# Vert_1.net
KiCad netlist of a schematic drawn in Altium Designer
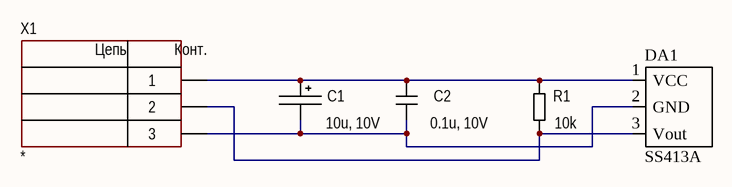
[diagram p0: Vert_1.SchDoc]

(export (version "E")
  (design (tool "Eeschema 10.0.6"))
  (components
    (comp (ref "C1")
      (value "10u, 10V")
      (footprint "TANTAL_A")
      (libsource (lib "Condensators") (part "TantalCap"))
    )
    (comp (ref "C2")
      (value "0.1u, 10V")
      (footprint "CH0603C")
      (libsource (lib "Condensators") (part "Capacitor"))
    )
    (comp (ref "DA1") (value "SS413A") (libsource (lib "BufLib") (part "SS413A")))
    (comp (ref "R1") (value "10k") (footprint "CH0603R") (libsource (lib "Resistors") (part "Resistor")))
    (comp (ref "X1")
      (value "*")
      (footprint "CON: WJ06-03P")
      (libsource (lib "Connectors") (part "3-Connector"))
    )
  )
  (nets
    (net (code "1") (name "Net-(DA1-GND)") (class "Default")
      (node (ref "C1") (pin "2") (pinfunction "2_2") (pintype "power_in"))
      (node (ref "C2") (pin "1") (pinfunction "1_1") (pintype "passive"))
      (node (ref "DA1") (pin "2") (pinfunction "GND_2") (pintype "passive"))
      (node (ref "X1") (pin "3") (pinfunction "3_3") (pintype "passive"))
    )
    (net (code "2") (name "Net-(DA1-VCC)") (class "Default")
      (node (ref "C1") (pin "1") (pinfunction "1_1") (pintype "power_in"))
      (node (ref "C2") (pin "2") (pinfunction "2_2") (pintype "passive"))
      (node (ref "DA1") (pin "1") (pinfunction "VCC_1") (pintype "passive"))
      (node (ref "R1") (pin "2") (pinfunction "2_2") (pintype "passive"))
      (node (ref "X1") (pin "1") (pinfunction "1_1") (pintype "passive"))
    )
    (net (code "3") (name "Net-(DA1-Vout)") (class "Default")
      (node (ref "DA1") (pin "3") (pinfunction "Vout_3") (pintype "passive"))
      (node (ref "R1") (pin "1") (pinfunction "1_1") (pintype "passive"))
      (node (ref "X1") (pin "2") (pinfunction "2_2") (pintype "passive"))
    )
  )
)
